# KarasolboxCont.net
KiCad netlist of a schematic drawn in EAGLE
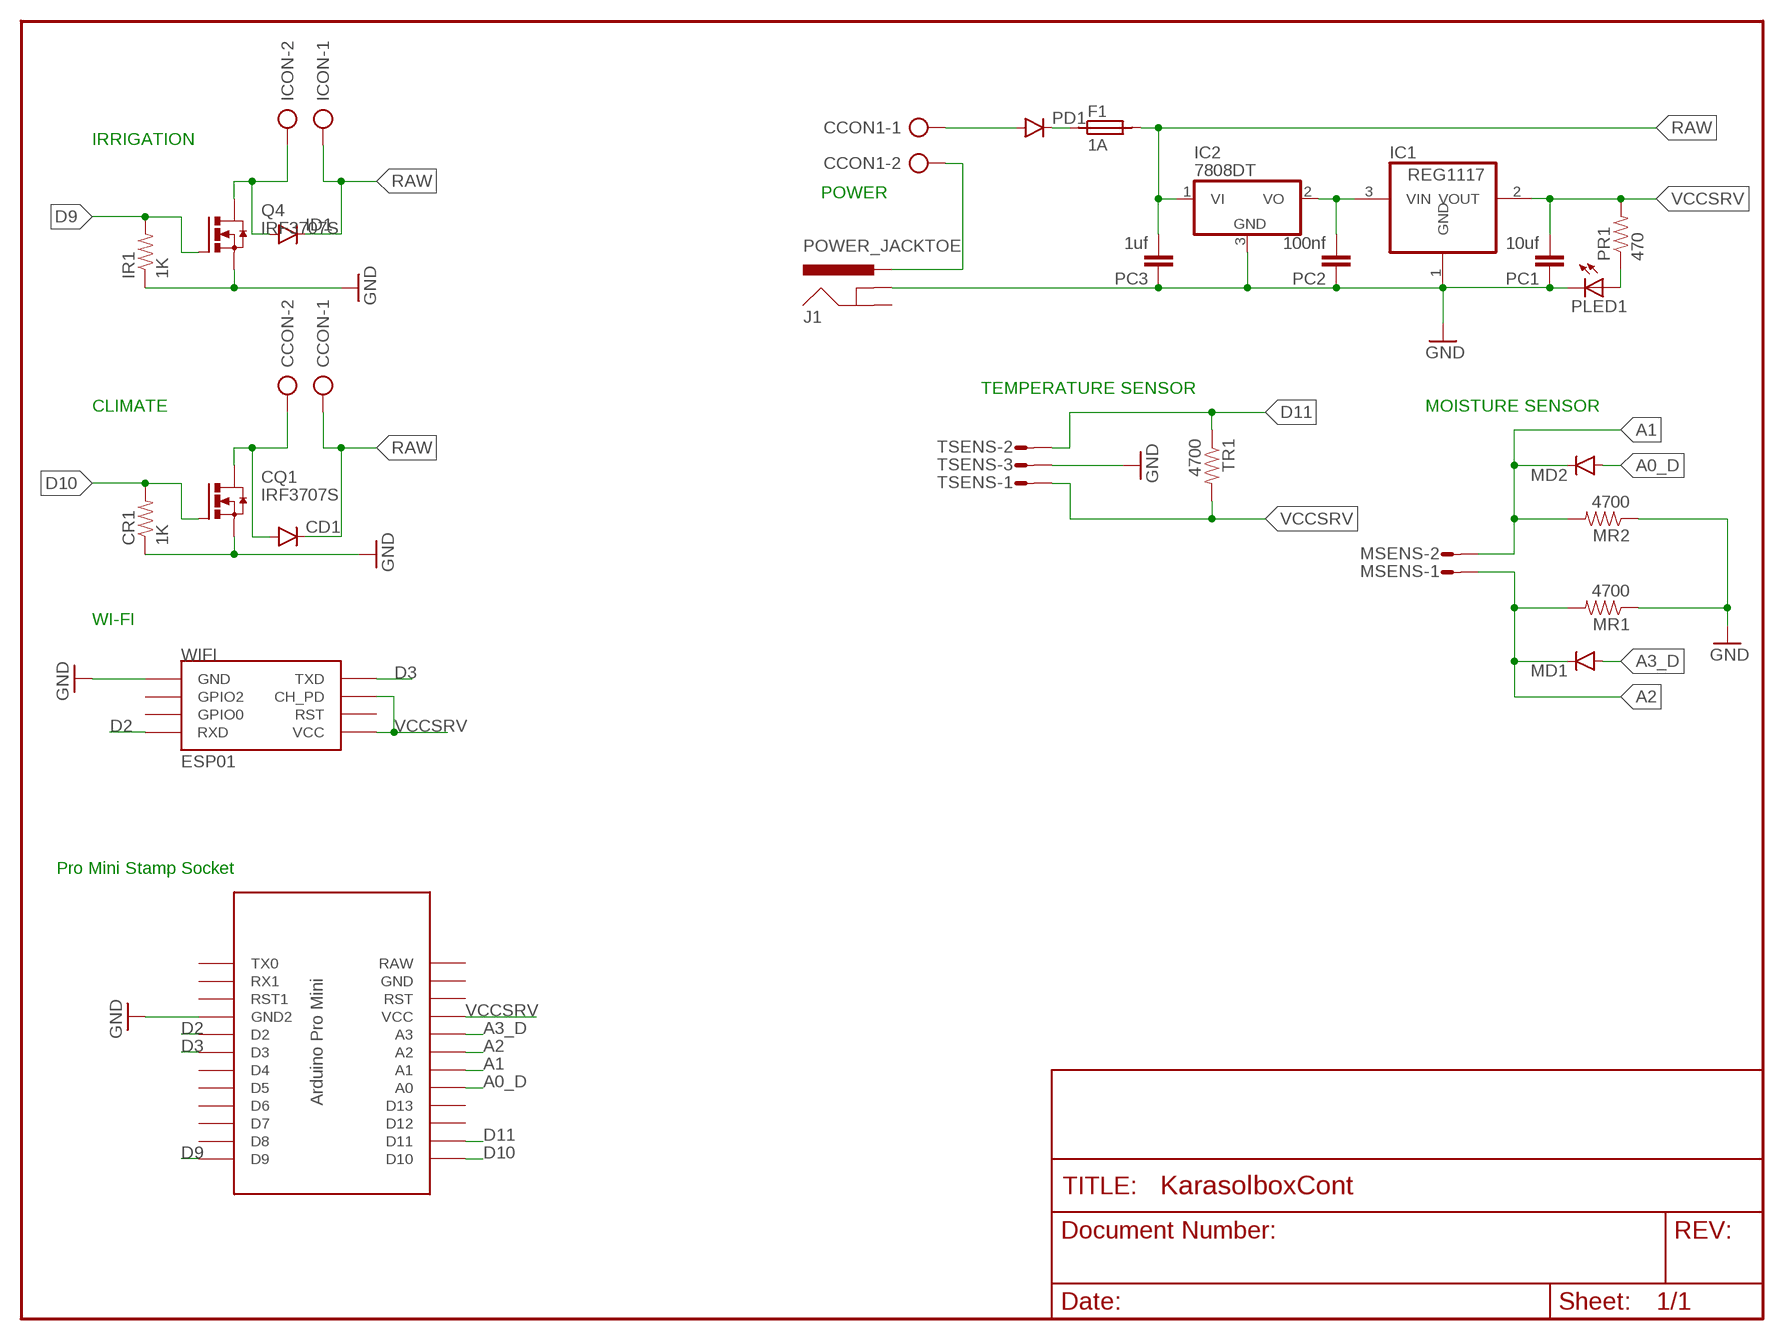
[diagram p0: schematic, sheet 1]

(export (version "E")
  (design (tool "Eeschema 10.0.6"))
  (components
    (comp (ref "CCON")
      (value "AK300/2")
      (footprint "eagle-import:AK300_2")
      (libsource (lib "eagle-import") (part "AK300/2"))
    )
    (comp (ref "CCON1")
      (value "AK300/2")
      (footprint "eagle-import:AK300_2")
      (libsource (lib "eagle-import") (part "AK300/2"))
    )
    (comp (ref "CD1")
      (value "DIODESMA")
      (footprint "eagle-import:SMA-DIODE")
      (libsource (lib "eagle-import") (part "DIODESMA"))
    )
    (comp (ref "CQ1")
      (value "IRF3707S")
      (footprint "eagle-import:D2PACK")
      (libsource (lib "eagle-import") (part "IRF3704S"))
    )
    (comp (ref "CR1")
      (value "1K")
      (footprint "eagle-import:0805")
      (libsource (lib "eagle-import") (part "RESISTOR0805-RES"))
    )
    (comp (ref "F1")
      (value "1A")
      (footprint "eagle-import:1820")
      (libsource (lib "eagle-import") (part "SIBA194600"))
    )
    (comp (ref "IC1")
      (value "REG1117")
      (footprint "eagle-import:SOT223")
      (libsource (lib "eagle-import") (part "REG1117"))
    )
    (comp (ref "IC2")
      (value "7808DT")
      (footprint "eagle-import:TO252")
      (libsource (lib "eagle-import") (part "78DT08"))
    )
    (comp (ref "ICON")
      (value "AK300/2")
      (footprint "eagle-import:AK300_2")
      (libsource (lib "eagle-import") (part "AK300/2"))
    )
    (comp (ref "ID1")
      (value "DIODESMA")
      (footprint "eagle-import:SMA-DIODE")
      (libsource (lib "eagle-import") (part "DIODESMA"))
    )
    (comp (ref "IR1")
      (value "1K")
      (footprint "eagle-import:0805")
      (libsource (lib "eagle-import") (part "RESISTOR0805-RES"))
    )
    (comp (ref "J1")
      (value "POWER_JACKTOE")
      (footprint "eagle-import:POWER_JACK_SMD_OVERPASTE_TOE")
      (libsource (lib "eagle-import") (part "POWER_JACKTOE"))
    )
    (comp (ref "MD1")
      (value "DIODESMA")
      (footprint "eagle-import:SMA-DIODE")
      (libsource (lib "eagle-import") (part "DIODESMA"))
    )
    (comp (ref "MD2")
      (value "DIODESMA")
      (footprint "eagle-import:SMA-DIODE")
      (libsource (lib "eagle-import") (part "DIODESMA"))
    )
    (comp (ref "MR1")
      (value "4700")
      (footprint "eagle-import:0805")
      (libsource (lib "eagle-import") (part "RESISTOR0805-RES"))
    )
    (comp (ref "MR2")
      (value "4700")
      (footprint "eagle-import:0805")
      (libsource (lib "eagle-import") (part "RESISTOR0805-RES"))
    )
    (comp (ref "MSENS")
      (value "S02P")
      (footprint "eagle-import:S02P")
      (libsource (lib "eagle-import") (part "S02P"))
    )
    (comp (ref "PC1")
      (value "10uf")
      (footprint "eagle-import:0805")
      (libsource (lib "eagle-import") (part "CAP0805"))
    )
    (comp (ref "PC2")
      (value "100nf")
      (footprint "eagle-import:0805")
      (libsource (lib "eagle-import") (part "CAP0805"))
    )
    (comp (ref "PC3")
      (value "1uf")
      (footprint "eagle-import:0805")
      (libsource (lib "eagle-import") (part "CAP0805"))
    )
    (comp (ref "PD1")
      (value "DIODESMA")
      (footprint "eagle-import:SMA-DIODE")
      (libsource (lib "eagle-import") (part "DIODESMA"))
    )
    (comp (ref "PLED1")
      (value "LEDCHIP-LED0805")
      (footprint "eagle-import:CHIP-LED0805")
      (libsource (lib "eagle-import") (part "LEDCHIP-LED0805"))
    )
    (comp (ref "PR1")
      (value "470")
      (footprint "eagle-import:0805")
      (libsource (lib "eagle-import") (part "RESISTOR0805-RES"))
    )
    (comp (ref "Q4")
      (value "IRF3707S")
      (footprint "eagle-import:D2PACK")
      (libsource (lib "eagle-import") (part "IRF3704S"))
    )
    (comp (ref "TR1")
      (value "4700")
      (footprint "eagle-import:0805")
      (libsource (lib "eagle-import") (part "RESISTOR0805-RES"))
    )
    (comp (ref "TSENS")
      (value "S03P")
      (footprint "eagle-import:S03P")
      (libsource (lib "eagle-import") (part "S03P"))
    )
    (comp (ref "U$1")
      (value "ABK-PRO-MINI")
      (footprint "eagle-import:ABK-PRO-MINI")
      (libsource (lib "eagle-import") (part "ABK-PRO-MINI"))
    )
    (comp (ref "WIFI")
      (value "ESP01")
      (footprint "eagle-import:ESP01")
      (libsource (lib "eagle-import") (part "ESP01"))
    )
  )
  (nets
    (net (code "1") (name "/D2") (class "Default")
      (node (ref "U$1") (pin "D2") (pinfunction "D2_D2") (pintype "bidirectional"))
      (node (ref "WIFI") (pin "RX") (pinfunction "RXD_RX") (pintype "bidirectional"))
    )
    (net (code "2") (name "/D3") (class "Default")
      (node (ref "U$1") (pin "D3") (pinfunction "D3_D3") (pintype "bidirectional"))
      (node (ref "WIFI") (pin "TX") (pinfunction "TXD_TX") (pintype "bidirectional"))
    )
    (net (code "3") (name "A0_D") (class "Default")
      (node (ref "MD2") (pin "A") (pinfunction "A_A") (pintype "passive"))
      (node (ref "U$1") (pin "A0") (pinfunction "A0_A0") (pintype "bidirectional"))
    )
    (net (code "4") (name "A1") (class "Default")
      (node (ref "MD2") (pin "C") (pinfunction "C_C") (pintype "passive"))
      (node (ref "MR2") (pin "2") (pinfunction "2_2") (pintype "passive"))
      (node (ref "MSENS") (pin "2") (pinfunction "S_2") (pintype "passive"))
      (node (ref "U$1") (pin "A1") (pinfunction "A1_A1") (pintype "bidirectional"))
    )
    (net (code "5") (name "A2") (class "Default")
      (node (ref "MD1") (pin "C") (pinfunction "C_C") (pintype "passive"))
      (node (ref "MR1") (pin "2") (pinfunction "2_2") (pintype "passive"))
      (node (ref "MSENS") (pin "1") (pinfunction "S_1") (pintype "passive"))
      (node (ref "U$1") (pin "A2") (pinfunction "A2_A2") (pintype "bidirectional"))
    )
    (net (code "6") (name "A3_D") (class "Default")
      (node (ref "MD1") (pin "A") (pinfunction "A_A") (pintype "passive"))
      (node (ref "U$1") (pin "A3") (pinfunction "A3_A3") (pintype "bidirectional"))
    )
    (net (code "7") (name "D9") (class "Default")
      (node (ref "IR1") (pin "2") (pinfunction "2_2") (pintype "passive"))
      (node (ref "Q4") (pin "1") (pinfunction "G_1") (pintype "passive"))
      (node (ref "U$1") (pin "D9") (pinfunction "D9_D9") (pintype "bidirectional"))
    )
    (net (code "8") (name "D10") (class "Default")
      (node (ref "CQ1") (pin "1") (pinfunction "G_1") (pintype "passive"))
      (node (ref "CR1") (pin "2") (pinfunction "2_2") (pintype "passive"))
      (node (ref "U$1") (pin "D10") (pinfunction "D10_D10") (pintype "bidirectional"))
    )
    (net (code "9") (name "D11") (class "Default")
      (node (ref "TR1") (pin "1") (pinfunction "1_1") (pintype "passive"))
      (node (ref "TSENS") (pin "2") (pinfunction "S_2") (pintype "passive"))
      (node (ref "U$1") (pin "D11") (pinfunction "D11_D11") (pintype "bidirectional"))
    )
    (net (code "10") (name "GND") (class "Default")
      (node (ref "CQ1") (pin "3") (pinfunction "S_3") (pintype "passive"))
      (node (ref "CR1") (pin "1") (pinfunction "1_1") (pintype "passive"))
      (node (ref "IC1") (pin "1") (pinfunction "GND_1") (pintype "power_in"))
      (node (ref "IC2") (pin "3") (pinfunction "GND_3") (pintype "passive"))
      (node (ref "IR1") (pin "1") (pinfunction "1_1") (pintype "passive"))
      (node (ref "J1") (pin "GND") (pinfunction "GNDBREAK_GND") (pintype "bidirectional"))
      (node (ref "MR1") (pin "1") (pinfunction "1_1") (pintype "passive"))
      (node (ref "MR2") (pin "1") (pinfunction "1_1") (pintype "passive"))
      (node (ref "PC1") (pin "1") (pinfunction "1_1") (pintype "passive"))
      (node (ref "PC2") (pin "1") (pinfunction "1_1") (pintype "passive"))
      (node (ref "PC3") (pin "1") (pinfunction "1_1") (pintype "passive"))
      (node (ref "PLED1") (pin "C") (pinfunction "C_C") (pintype "passive"))
      (node (ref "Q4") (pin "3") (pinfunction "S_3") (pintype "passive"))
      (node (ref "TSENS") (pin "3") (pinfunction "S_3") (pintype "passive"))
      (node (ref "U$1") (pin "GND1") (pinfunction "GND2_GND1") (pintype "bidirectional"))
      (node (ref "WIFI") (pin "GND") (pinfunction "GND_GND") (pintype "bidirectional"))
    )
    (net (code "11") (name "Net-(CCON1A-KL)") (class "Default")
      (node (ref "CCON1") (pin "1") (pinfunction "KL_1") (pintype "passive"))
      (node (ref "PD1") (pin "A") (pinfunction "A_A") (pintype "passive"))
    )
    (net (code "12") (name "Net-(CCON1B-KL)") (class "Default")
      (node (ref "CCON1") (pin "2") (pinfunction "KL_2") (pintype "passive"))
      (node (ref "J1") (pin "VIN0") (pinfunction "PWR_VIN0") (pintype "bidirectional"))
    )
    (net (code "13") (name "Net-(CCONB-KL)") (class "Default")
      (node (ref "CCON") (pin "2") (pinfunction "KL_2") (pintype "passive"))
      (node (ref "CD1") (pin "A") (pinfunction "A_A") (pintype "passive"))
      (node (ref "CQ1") (pin "2") (pinfunction "D_2") (pintype "passive"))
    )
    (net (code "14") (name "Net-(F1-Pad1)") (class "Default")
      (node (ref "F1") (pin "1") (pinfunction "1_1") (pintype "passive"))
      (node (ref "PD1") (pin "C") (pinfunction "C_C") (pintype "passive"))
    )
    (net (code "15") (name "Net-(IC1-VIN)") (class "Default")
      (node (ref "IC1") (pin "3") (pinfunction "VIN_3") (pintype "input"))
      (node (ref "IC2") (pin "2") (pinfunction "VO_2") (pintype "passive"))
      (node (ref "PC2") (pin "2") (pinfunction "2_2") (pintype "passive"))
    )
    (net (code "16") (name "Net-(ICONB-KL)") (class "Default")
      (node (ref "ICON") (pin "2") (pinfunction "KL_2") (pintype "passive"))
      (node (ref "ID1") (pin "A") (pinfunction "A_A") (pintype "passive"))
      (node (ref "Q4") (pin "2") (pinfunction "D_2") (pintype "passive"))
    )
    (net (code "17") (name "Net-(PLED1-PadA)") (class "Default")
      (node (ref "PLED1") (pin "A") (pinfunction "A_A") (pintype "passive"))
      (node (ref "PR1") (pin "1") (pinfunction "1_1") (pintype "passive"))
    )
    (net (code "18") (name "RAW") (class "Default")
      (node (ref "CCON") (pin "1") (pinfunction "KL_1") (pintype "passive"))
      (node (ref "CD1") (pin "C") (pinfunction "C_C") (pintype "passive"))
      (node (ref "F1") (pin "2") (pinfunction "2_2") (pintype "passive"))
      (node (ref "IC2") (pin "1") (pinfunction "VI_1") (pintype "input"))
      (node (ref "ICON") (pin "1") (pinfunction "KL_1") (pintype "passive"))
      (node (ref "ID1") (pin "C") (pinfunction "C_C") (pintype "passive"))
      (node (ref "PC3") (pin "2") (pinfunction "2_2") (pintype "passive"))
    )
    (net (code "19") (name "VCCSRV") (class "Default")
      (node (ref "IC1") (pin "2") (pinfunction "VOUT_2") (pintype "output"))
      (node (ref "PC1") (pin "2") (pinfunction "2_2") (pintype "passive"))
      (node (ref "PR1") (pin "2") (pinfunction "2_2") (pintype "passive"))
      (node (ref "TR1") (pin "2") (pinfunction "2_2") (pintype "passive"))
      (node (ref "TSENS") (pin "1") (pinfunction "S_1") (pintype "passive"))
      (node (ref "U$1") (pin "VCC") (pinfunction "VCC_VCC") (pintype "bidirectional"))
      (node (ref "WIFI") (pin "CH_PD") (pinfunction "CH_PD_CH_PD") (pintype "bidirectional"))
      (node (ref "WIFI") (pin "VCC") (pinfunction "VCC_VCC") (pintype "bidirectional"))
    )
    (net (code "20") (name "unconnected-(J1-GND-PadP$4)") (class "Default")
      (node (ref "J1") (pin "P$4") (pinfunction "GND_P$4") (pintype "bidirectional"))
    )
    (net (code "21") (name "unconnected-(U$1-PadD4)") (class "Default")
      (node (ref "U$1") (pin "D4") (pinfunction "D4_D4") (pintype "bidirectional"))
    )
    (net (code "22") (name "unconnected-(U$1-PadD5)") (class "Default")
      (node (ref "U$1") (pin "D5") (pinfunction "D5_D5") (pintype "bidirectional"))
    )
    (net (code "23") (name "unconnected-(U$1-PadD6)") (class "Default")
      (node (ref "U$1") (pin "D6") (pinfunction "D6_D6") (pintype "bidirectional"))
    )
    (net (code "24") (name "unconnected-(U$1-PadD7)") (class "Default")
      (node (ref "U$1") (pin "D7") (pinfunction "D7_D7") (pintype "bidirectional"))
    )
    (net (code "25") (name "unconnected-(U$1-PadD8)") (class "Default")
      (node (ref "U$1") (pin "D8") (pinfunction "D8_D8") (pintype "bidirectional"))
    )
    (net (code "26") (name "unconnected-(U$1-PadD12)") (class "Default")
      (node (ref "U$1") (pin "D12") (pinfunction "D12_D12") (pintype "bidirectional"))
    )
    (net (code "27") (name "unconnected-(U$1-PadD13)") (class "Default")
      (node (ref "U$1") (pin "D13") (pinfunction "D13_D13") (pintype "bidirectional"))
    )
    (net (code "28") (name "unconnected-(U$1-PadGND)") (class "Default")
      (node (ref "U$1") (pin "GND") (pinfunction "GND_GND") (pintype "bidirectional"))
    )
    (net (code "29") (name "unconnected-(U$1-PadRAW)") (class "Default")
      (node (ref "U$1") (pin "RAW") (pinfunction "RAW_RAW") (pintype "bidirectional"))
    )
    (net (code "30") (name "unconnected-(U$1-PadRST)") (class "Default")
      (node (ref "U$1") (pin "RST") (pinfunction "RST_RST") (pintype "bidirectional"))
    )
    (net (code "31") (name "unconnected-(U$1-PadRST1)") (class "Default")
      (node (ref "U$1") (pin "RST1") (pinfunction "RST1_RST1") (pintype "bidirectional"))
    )
    (net (code "32") (name "unconnected-(U$1-PadRX1)") (class "Default")
      (node (ref "U$1") (pin "RX1") (pinfunction "RX1_RX1") (pintype "bidirectional"))
    )
    (net (code "33") (name "unconnected-(U$1-PadTX0)") (class "Default")
      (node (ref "U$1") (pin "TX0") (pinfunction "TX0_TX0") (pintype "bidirectional"))
    )
    (net (code "34") (name "unconnected-(WIFI-PadGPIO0)") (class "Default")
      (node (ref "WIFI") (pin "GPIO0") (pinfunction "GPIO0_GPIO0") (pintype "bidirectional"))
    )
    (net (code "35") (name "unconnected-(WIFI-PadGPIO2)") (class "Default")
      (node (ref "WIFI") (pin "GPIO2") (pinfunction "GPIO2_GPIO2") (pintype "bidirectional"))
    )
    (net (code "36") (name "unconnected-(WIFI-PadRST)") (class "Default")
      (node (ref "WIFI") (pin "RST") (pinfunction "RST_RST") (pintype "bidirectional"))
    )
  )
)
